# MCP73831_BMS.net
KiCad netlist of a schematic drawn in Altium Designer
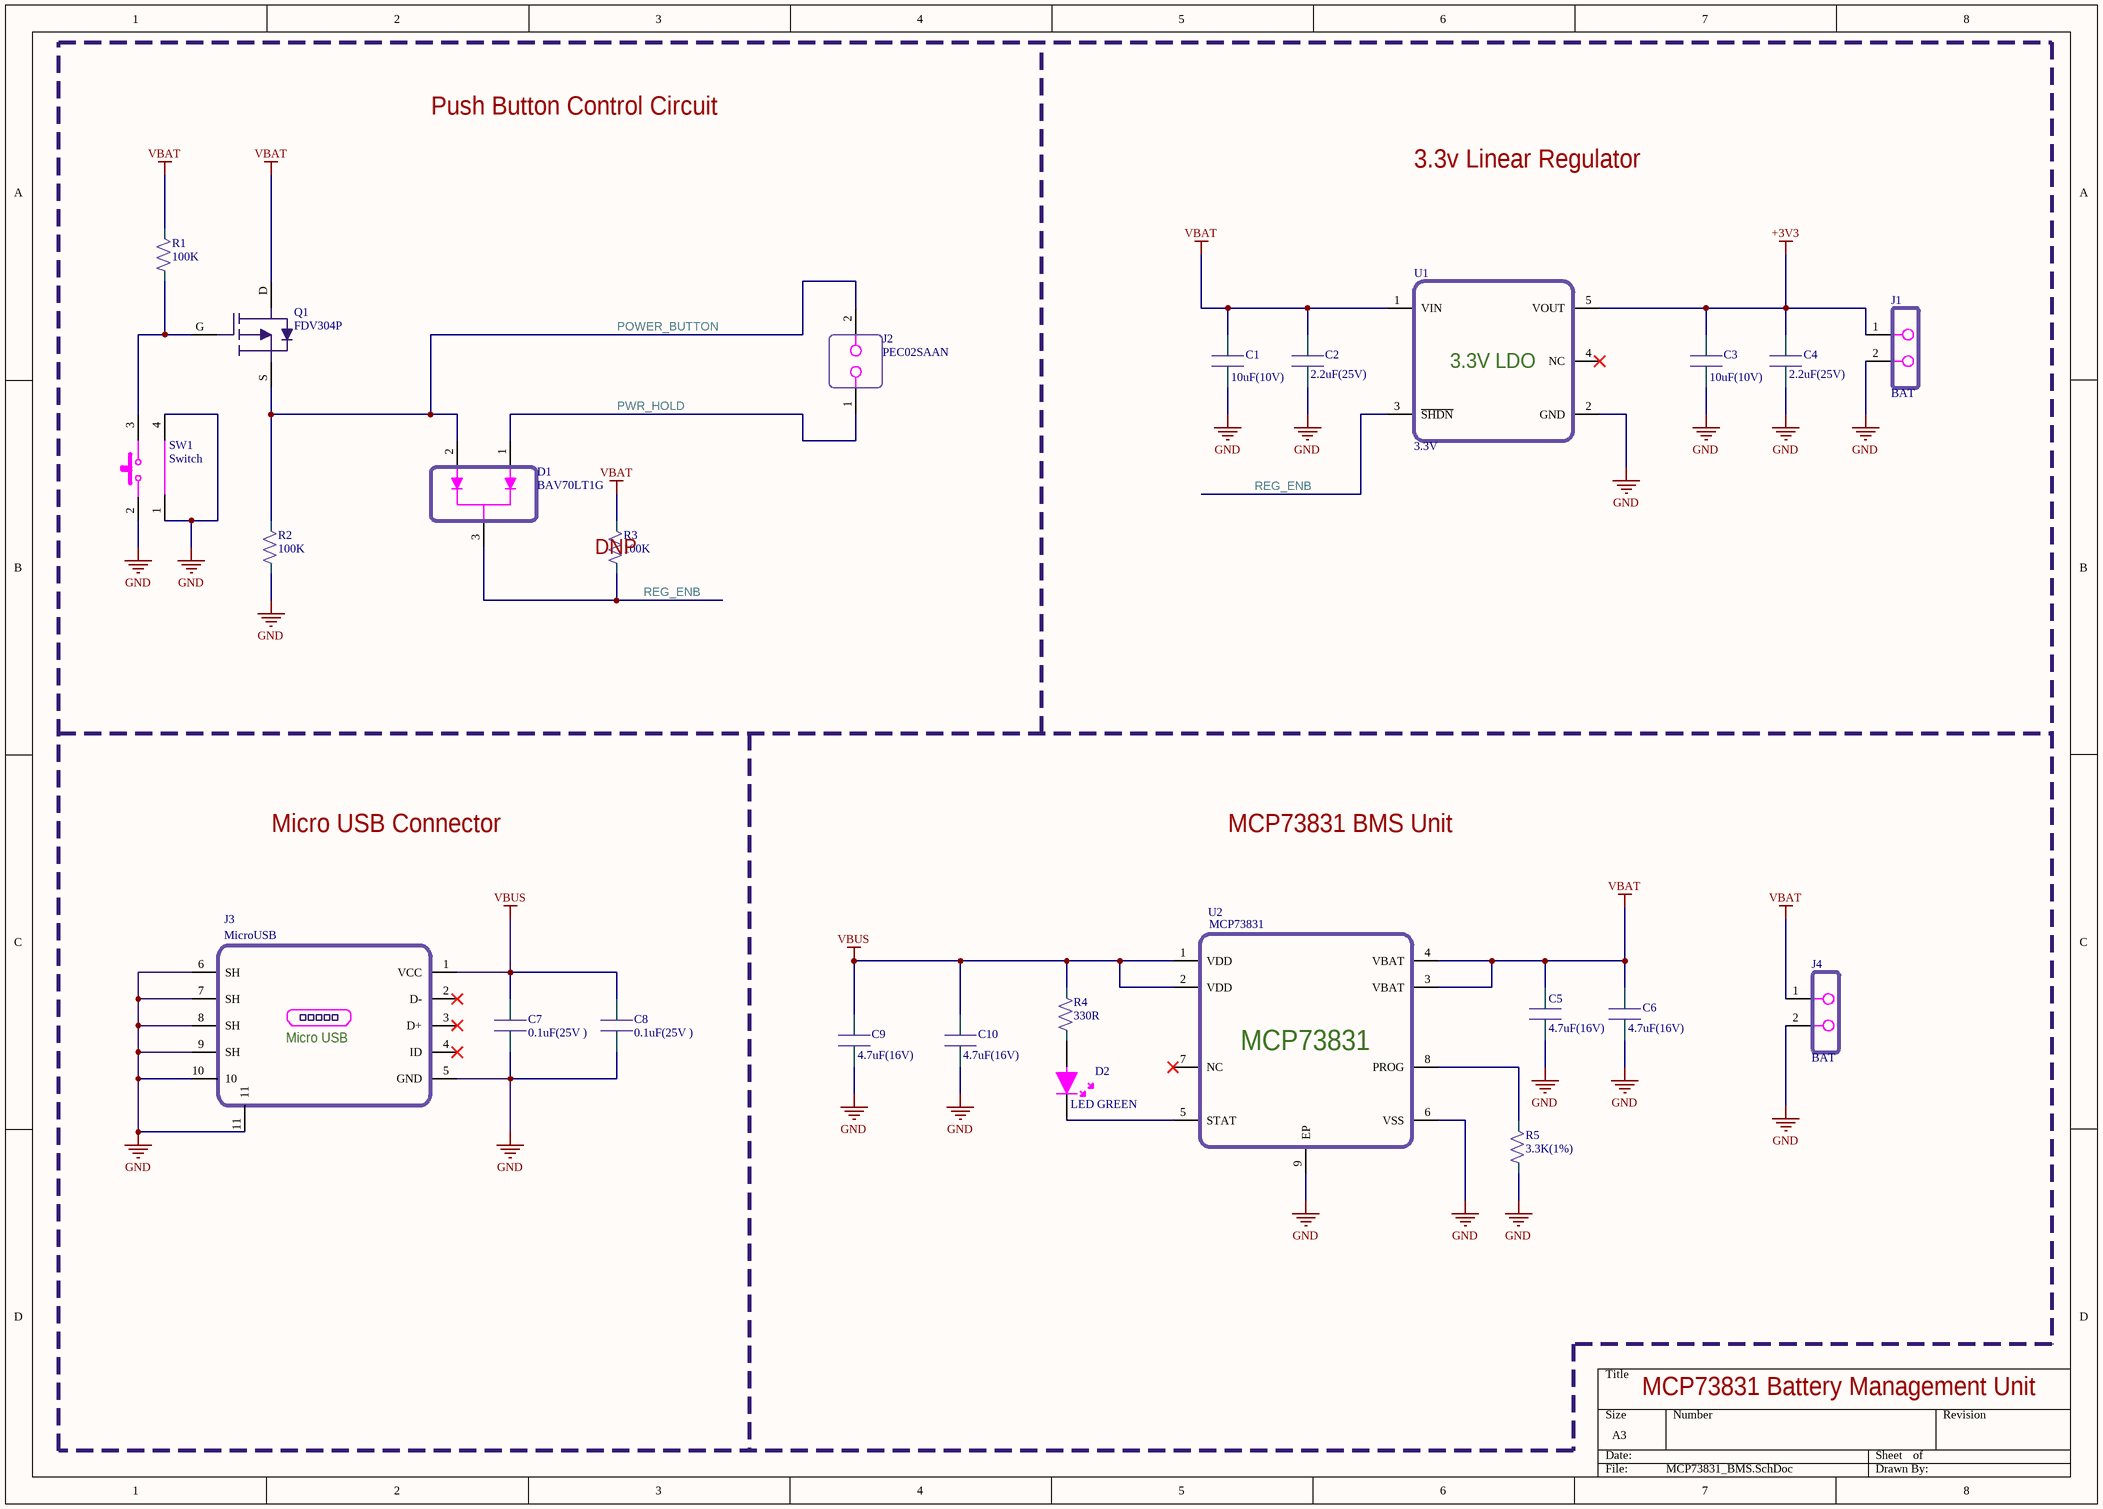
[diagram p0: MCP73831_BMS.SchDoc]

(export (version "E")
  (design (tool "Eeschema 10.0.6"))
  (components
    (comp (ref "C1")
      (value "10uF(10V)")
      (footprint "CAPACITOR_0402")
      (description "10µF ±20% 10V Ceramic Capacitor X5R 0402 (1005 Metric)")
      (fields
        (field (name "MANUFACTURERPARTNUMBER") "CL05A106MP8NUB8")
        (field (name "MANUFACTURER") "Samsung Electro-Mechanics")
      )
      (libsource (lib "Capacitors") (part "CL05A106MP8NUB8"))
    )
    (comp (ref "C2")
      (value "2.2uF(25V)")
      (footprint "CAPACITOR_0402")
      (description "2.2 µF ±10% 25V Ceramic Capacitor X5R 0402 (1005 Metric)")
      (fields
        (field (name "MANUAFCTURERPARTNUMBER") "GRT155R61E225KE13D")
        (field (name "MANUFACTURER") "Murata Electronics")
      )
      (libsource (lib "Capacitors") (part "GRT155R61E225KE13D"))
    )
    (comp (ref "C3")
      (value "10uF(10V)")
      (footprint "CAPACITOR_0402")
      (description "10µF ±20% 10V Ceramic Capacitor X5R 0402 (1005 Metric)")
      (fields
        (field (name "MANUFACTURERPARTNUMBER") "CL05A106MP8NUB8")
        (field (name "MANUFACTURER") "Samsung Electro-Mechanics")
      )
      (libsource (lib "Capacitors") (part "CL05A106MP8NUB8"))
    )
    (comp (ref "C4")
      (value "2.2uF(25V)")
      (footprint "CAPACITOR_0402")
      (description "2.2 µF ±10% 25V Ceramic Capacitor X5R 0402 (1005 Metric)")
      (fields
        (field (name "MANUAFCTURERPARTNUMBER") "GRT155R61E225KE13D")
        (field (name "MANUFACTURER") "Murata Electronics")
      )
      (libsource (lib "Capacitors") (part "GRT155R61E225KE13D"))
    )
    (comp (ref "C5")
      (value "4.7uF(16V)")
      (footprint "CAPACITOR_0402")
      (description "4.7µF ±20% 16V Ceramic Capacitor X5R 0402 (1005 Metric)")
      (fields
        (field (name "MANUFACTURERPARTNUMBER") "0402YD475MAT2A")
        (field (name "MANUFACTURER") "AVX Corporation")
      )
      (libsource (lib "Capacitors") (part "0402YD475MAT2A"))
    )
    (comp (ref "C6")
      (value "4.7uF(16V)")
      (footprint "CAPACITOR_0402")
      (description "4.7µF ±20% 16V Ceramic Capacitor X5R 0402 (1005 Metric)")
      (fields
        (field (name "MANUFACTURERPARTNUMBER") "0402YD475MAT2A")
        (field (name "MANUFACTURER") "AVX Corporation")
      )
      (libsource (lib "Capacitors") (part "0402YD475MAT2A"))
    )
    (comp (ref "C7")
      (value "0.1uF(25V )")
      (footprint "CAPACITOR_0402")
      (description "0.1µF ±10% 25V Ceramic Capacitor X7R 0402 (1005 Metric)")
      (fields
        (field (name "MANUFACTURERPARTNUMBER") "GRM155R71E104KE14J")
        (field (name "MANUFACTURER") "Murata Electronics")
      )
      (libsource (lib "Capacitors") (part "GRM155R71E104KE14J"))
    )
    (comp (ref "C8")
      (value "0.1uF(25V )")
      (footprint "CAPACITOR_0402")
      (description "0.1µF ±10% 25V Ceramic Capacitor X7R 0402 (1005 Metric)")
      (fields
        (field (name "MANUFACTURERPARTNUMBER") "GRM155R71E104KE14J")
        (field (name "MANUFACTURER") "Murata Electronics")
      )
      (libsource (lib "Capacitors") (part "GRM155R71E104KE14J"))
    )
    (comp (ref "C9")
      (value "4.7uF(16V)")
      (footprint "CAPACITOR_0402")
      (description "4.7µF ±20% 16V Ceramic Capacitor X5R 0402 (1005 Metric)")
      (fields
        (field (name "MANUFACTURERPARTNUMBER") "0402YD475MAT2A")
        (field (name "MANUFACTURER") "AVX Corporation")
      )
      (libsource (lib "Capacitors") (part "0402YD475MAT2A"))
    )
    (comp (ref "C10")
      (value "4.7uF(16V)")
      (footprint "CAPACITOR_0402")
      (description "4.7µF ±20% 16V Ceramic Capacitor X5R 0402 (1005 Metric)")
      (fields
        (field (name "MANUFACTURERPARTNUMBER") "0402YD475MAT2A")
        (field (name "MANUFACTURER") "AVX Corporation")
      )
      (libsource (lib "Capacitors") (part "0402YD475MAT2A"))
    )
    (comp (ref "D1")
      (value "BAV70LT1G")
      (footprint "SOT-23_3LEAD - BAV70")
      (description "Diode Array 1 Pair Common Cathode Standard 200mA (DC) Surface Mount TO-236-3, SC-59, SOT-23-3")
      (fields (field (name "MANUFACTURER") "ON Semiconductor"))
      (libsource (lib "Diodes") (part "BAV70LT1G"))
    )
    (comp (ref "D2")
      (value "LED GREEN")
      (footprint "0603_LED")
      (description "Green 570nm LED Indication - Discrete 2.1V 0603 (1608 Metric)")
      (fields (field (name "MANUFACTURER PART NUMBER") "XZVG53W-8"))
      (libsource (lib "Diodes") (part "XZVG53W-8"))
    )
    (comp (ref "J1")
      (value "BAT")
      (footprint "SM02B-SRSS-TB(LF)(SN)")
      (description "Connector Header Surface Mount, Right Angle 2 position 0.039\" (1.00mm)")
      (fields
        (field (name "MANUFACTURERPARTNUMBER") "SM02B-SRSS-TB(LF)(SN)")
        (field (name "MANUFACTURER") "JST Sales America Inc.")
      )
      (libsource (lib "connectors") (part "SM02B-SRSS-TB(LF)(SN)"))
    )
    (comp (ref "J2")
      (value "PEC02SAAN")
      (footprint "P2.541X2HDR")
      (description "Connector Header Through Hole 2 position 0.100\" (2.54mm)")
      (libsource (lib "connectors") (part "PEC02SAAN"))
    )
    (comp (ref "J3")
      (value "MicroUSB")
      (footprint "Micro USB")
      (description "USB - micro B USB 2.0 Receptacle Connector 5 Position Surface Mount, Right Angle; Through Hole")
      (fields
        (field (name "MANUFACTURERPARTNUMBER") "629105150521")
        (field (name "MANUFACTURER") "Würth Elektronik")
      )
      (libsource (lib "Connectors") (part "629105150521"))
    )
    (comp (ref "J4")
      (value "BAT")
      (footprint "SM02B-SRSS-TB(LF)(SN)")
      (description "Connector Header Surface Mount, Right Angle 2 position 0.039\" (1.00mm)")
      (fields
        (field (name "MANUFACTURERPARTNUMBER") "SM02B-SRSS-TB(LF)(SN)")
        (field (name "MANUFACTURER") "JST Sales America Inc.")
      )
      (libsource (lib "connectors") (part "SM02B-SRSS-TB(LF)(SN)"))
    )
    (comp (ref "Q1")
      (value "FDV304P")
      (footprint "SOT-23_3LEAD")
      (description "P-Channel 460mA (Ta) 350mW (Ta) Surface Mount SOT-23")
      (fields (field (name "MANUFACTURER") "ON Semiconductor"))
      (libsource (lib "Integrated Circuits") (part "FDV304P"))
    )
    (comp (ref "R1")
      (value "100K")
      (footprint "RESISTOR_0402")
      (description "100 kOhms ±5% 0.1W, 1/10W Chip Resistor 0402 (1005 Metric) Automotive AEC-Q200 Thick Film")
      (fields
        (field (name "MANUFACTURERPARTNUMBER") "ERJ-2GEJ104X")
        (field (name "MANUFACTURER") "Panasonic Electronic Components")
      )
      (libsource (lib "Resistors") (part "ERJ-2GEJ104X"))
    )
    (comp (ref "R2")
      (value "100K")
      (footprint "RESISTOR_0402")
      (description "100 kOhms ±5% 0.1W, 1/10W Chip Resistor 0402 (1005 Metric) Automotive AEC-Q200 Thick Film")
      (fields
        (field (name "MANUFACTURERPARTNUMBER") "ERJ-2GEJ104X")
        (field (name "MANUFACTURER") "Panasonic Electronic Components")
      )
      (libsource (lib "Resistors") (part "ERJ-2GEJ104X"))
    )
    (comp (ref "R3")
      (value "100K")
      (footprint "RESISTOR_0402")
      (description "100 kOhms ±5% 0.1W, 1/10W Chip Resistor 0402 (1005 Metric) Automotive AEC-Q200 Thick Film")
      (fields
        (field (name "MANUFACTURERPARTNUMBER") "ERJ-2GEJ104X")
        (field (name "MANUFACTURER") "Panasonic Electronic Components")
      )
      (libsource (lib "Resistors") (part "ERJ-2GEJ104X"))
    )
    (comp (ref "R4")
      (value "330R")
      (footprint "RESISTOR_0402")
      (fields
        (field (name "MANUFACTURERPARTNUMBER") "CRGCQ0603J330R")
        (field (name "MANUFACTURER") "TE Connectivity Passive Product")
      )
      (libsource (lib "Resistors") (part "CRGCQ0603J330R"))
    )
    (comp (ref "R5")
      (value "3.3K(1%)")
      (footprint "RESISTOR_0402")
      (fields
        (field (name "MANUFACTURERPARTNUMBER") "RK73H1ETTP3301F")
        (field (name "MANUFACTURER") "KOA Speer Electronics, Inc.")
      )
      (libsource (lib "Resistors") (part "RK73H1ETTP3301F"))
    )
    (comp (ref "SW1")
      (value "Switch")
      (footprint "right angle through hole switch")
      (description "Tactile Switch SPST-NO Side Actuated Through Hole, Right Angle")
      (fields
        (field (name "MANUFACTURERPARTNUMBER") "1301.9502")
        (field (name "MANUFACTURER") "Schurter Inc.")
      )
      (libsource (lib "connectors") (part "1301.9502"))
    )
    (comp (ref "U1")
      (value "3.3V")
      (footprint "SOT23-5LEAD")
      (description "LDO Voltage Regulators Ultra Low Iq LDO")
      (fields
        (field (name "MANUAFCTURERPARTNUMBER") "MCP1812BT-033/OT")
        (field (name "MANUFACTURER") "Microchip Technology")
      )
      (libsource (lib "Integrated Circuits") (part "MCP1812BT-033/OT"))
    )
    (comp (ref "U2")
      (value "MCP73831")
      (footprint "8VFDFN")
      (description "Charger IC Lithium Ion/Polymer 8-DFN (2x3)")
      (fields
        (field (name "MANUFACTURERPARTNUMBER") "MCP73831T-2DCI/MC")
        (field (name "MANUFACTURER") "Microchip Technology")
      )
      (libsource (lib "Integrated Circuits") (part "MCP73831T-2DCI/MC"))
    )
  )
  (nets
    (net (code "1") (name "+3V3") (class "Default")
      (node (ref "C3") (pin "2") (pinfunction "2_2") (pintype "passive"))
      (node (ref "C4") (pin "2") (pinfunction "2_2") (pintype "passive"))
      (node (ref "J1") (pin "1") (pinfunction "1_1") (pintype "passive"))
      (node (ref "U1") (pin "5") (pinfunction "VOUT_5") (pintype "passive"))
    )
    (net (code "2") (name "/POWER_BUTTON") (class "Default")
      (node (ref "D1") (pin "2") (pinfunction "2_2") (pintype "passive"))
      (node (ref "J2") (pin "2") (pinfunction "2_2") (pintype "passive"))
      (node (ref "Q1") (pin "S") (pinfunction "S_S") (pintype "passive"))
      (node (ref "R2") (pin "2") (pinfunction "2_2") (pintype "passive"))
    )
    (net (code "3") (name "/PWR_HOLD") (class "Default")
      (node (ref "D1") (pin "1") (pinfunction "1_1") (pintype "passive"))
      (node (ref "J2") (pin "1") (pinfunction "1_1") (pintype "passive"))
    )
    (net (code "4") (name "/REG_ENB") (class "Default")
      (node (ref "D1") (pin "3") (pinfunction "3_3") (pintype "passive"))
      (node (ref "R3") (pin "1") (pinfunction "1_1") (pintype "passive"))
      (node (ref "U1") (pin "3") (pinfunction "~{SHDN}_3") (pintype "passive"))
    )
    (net (code "5") (name "GND") (class "Default")
      (node (ref "C1") (pin "1") (pinfunction "1_1") (pintype "passive"))
      (node (ref "C10") (pin "1") (pinfunction "1_1") (pintype "passive"))
      (node (ref "C2") (pin "1") (pinfunction "1_1") (pintype "passive"))
      (node (ref "C3") (pin "1") (pinfunction "1_1") (pintype "passive"))
      (node (ref "C4") (pin "1") (pinfunction "1_1") (pintype "passive"))
      (node (ref "C5") (pin "1") (pinfunction "1_1") (pintype "passive"))
      (node (ref "C6") (pin "1") (pinfunction "1_1") (pintype "passive"))
      (node (ref "C7") (pin "1") (pinfunction "1_1") (pintype "passive"))
      (node (ref "C8") (pin "1") (pinfunction "1_1") (pintype "passive"))
      (node (ref "C9") (pin "1") (pinfunction "1_1") (pintype "passive"))
      (node (ref "J1") (pin "2") (pinfunction "2_2") (pintype "passive"))
      (node (ref "J3") (pin "10") (pinfunction "10_10") (pintype "passive"))
      (node (ref "J3") (pin "11") (pinfunction "11_11") (pintype "passive"))
      (node (ref "J3") (pin "5") (pinfunction "GND_5") (pintype "passive"))
      (node (ref "J3") (pin "6") (pinfunction "SH_6") (pintype "passive"))
      (node (ref "J3") (pin "7") (pinfunction "SH_7") (pintype "passive"))
      (node (ref "J3") (pin "8") (pinfunction "SH_8") (pintype "passive"))
      (node (ref "J3") (pin "9") (pinfunction "SH_9") (pintype "passive"))
      (node (ref "J4") (pin "2") (pinfunction "2_2") (pintype "passive"))
      (node (ref "R2") (pin "1") (pinfunction "1_1") (pintype "passive"))
      (node (ref "R5") (pin "1") (pinfunction "1_1") (pintype "passive"))
      (node (ref "SW1") (pin "1") (pinfunction "1_1") (pintype "passive"))
      (node (ref "SW1") (pin "2") (pinfunction "2_2") (pintype "passive"))
      (node (ref "SW1") (pin "4") (pinfunction "4_4") (pintype "passive"))
      (node (ref "U1") (pin "2") (pinfunction "GND_2") (pintype "passive"))
      (node (ref "U2") (pin "6") (pinfunction "VSS_6") (pintype "passive"))
      (node (ref "U2") (pin "9") (pinfunction "EP_9") (pintype "passive"))
    )
    (net (code "6") (name "Net-(D2-Pad1)") (class "Default")
      (node (ref "D2") (pin "1") (pinfunction "1_1") (pintype "passive"))
      (node (ref "R4") (pin "1") (pinfunction "1_1") (pintype "passive"))
    )
    (net (code "7") (name "Net-(Q1-PadG)") (class "Default")
      (node (ref "Q1") (pin "G") (pinfunction "G_G") (pintype "passive"))
      (node (ref "R1") (pin "1") (pinfunction "1_1") (pintype "passive"))
      (node (ref "SW1") (pin "3") (pinfunction "3_3") (pintype "passive"))
    )
    (net (code "8") (name "Net-(U2-PROG)") (class "Default")
      (node (ref "R5") (pin "2") (pinfunction "2_2") (pintype "passive"))
      (node (ref "U2") (pin "8") (pinfunction "PROG_8") (pintype "passive"))
    )
    (net (code "9") (name "Net-(U2-STAT)") (class "Default")
      (node (ref "D2") (pin "2") (pinfunction "2_2") (pintype "passive"))
      (node (ref "U2") (pin "5") (pinfunction "STAT_5") (pintype "passive"))
    )
    (net (code "10") (name "VBAT") (class "Default")
      (node (ref "C1") (pin "2") (pinfunction "2_2") (pintype "passive"))
      (node (ref "C2") (pin "2") (pinfunction "2_2") (pintype "passive"))
      (node (ref "C5") (pin "2") (pinfunction "2_2") (pintype "passive"))
      (node (ref "C6") (pin "2") (pinfunction "2_2") (pintype "passive"))
      (node (ref "J4") (pin "1") (pinfunction "1_1") (pintype "passive"))
      (node (ref "Q1") (pin "D") (pinfunction "D_D") (pintype "passive"))
      (node (ref "R1") (pin "2") (pinfunction "2_2") (pintype "passive"))
      (node (ref "R3") (pin "2") (pinfunction "2_2") (pintype "passive"))
      (node (ref "U1") (pin "1") (pinfunction "VIN_1") (pintype "passive"))
      (node (ref "U2") (pin "3") (pinfunction "VBAT_3") (pintype "passive"))
      (node (ref "U2") (pin "4") (pinfunction "VBAT_4") (pintype "passive"))
    )
    (net (code "11") (name "VBUS") (class "Default")
      (node (ref "C10") (pin "2") (pinfunction "2_2") (pintype "passive"))
      (node (ref "C7") (pin "2") (pinfunction "2_2") (pintype "passive"))
      (node (ref "C8") (pin "2") (pinfunction "2_2") (pintype "passive"))
      (node (ref "C9") (pin "2") (pinfunction "2_2") (pintype "passive"))
      (node (ref "J3") (pin "1") (pinfunction "VCC_1") (pintype "passive"))
      (node (ref "R4") (pin "2") (pinfunction "2_2") (pintype "passive"))
      (node (ref "U2") (pin "1") (pinfunction "VDD_1") (pintype "passive"))
      (node (ref "U2") (pin "2") (pinfunction "VDD_2") (pintype "passive"))
    )
    (net (code "12") (name "unconnected-(J3-D+-Pad3)") (class "Default")
      (node (ref "J3") (pin "3") (pinfunction "D+_3") (pintype "passive+no_connect"))
    )
    (net (code "13") (name "unconnected-(J3-D--Pad2)") (class "Default")
      (node (ref "J3") (pin "2") (pinfunction "D-_2") (pintype "passive+no_connect"))
    )
    (net (code "14") (name "unconnected-(J3-ID-Pad4)") (class "Default")
      (node (ref "J3") (pin "4") (pinfunction "ID_4") (pintype "passive+no_connect"))
    )
    (net (code "15") (name "unconnected-(U1-NC-Pad4)") (class "Default")
      (node (ref "U1") (pin "4") (pinfunction "NC_4") (pintype "passive+no_connect"))
    )
    (net (code "16") (name "unconnected-(U2-NC-Pad7)") (class "Default")
      (node (ref "U2") (pin "7") (pinfunction "NC_7") (pintype "passive+no_connect"))
    )
  )
)
